# board.net
KiCad netlist of a schematic drawn in EAGLE
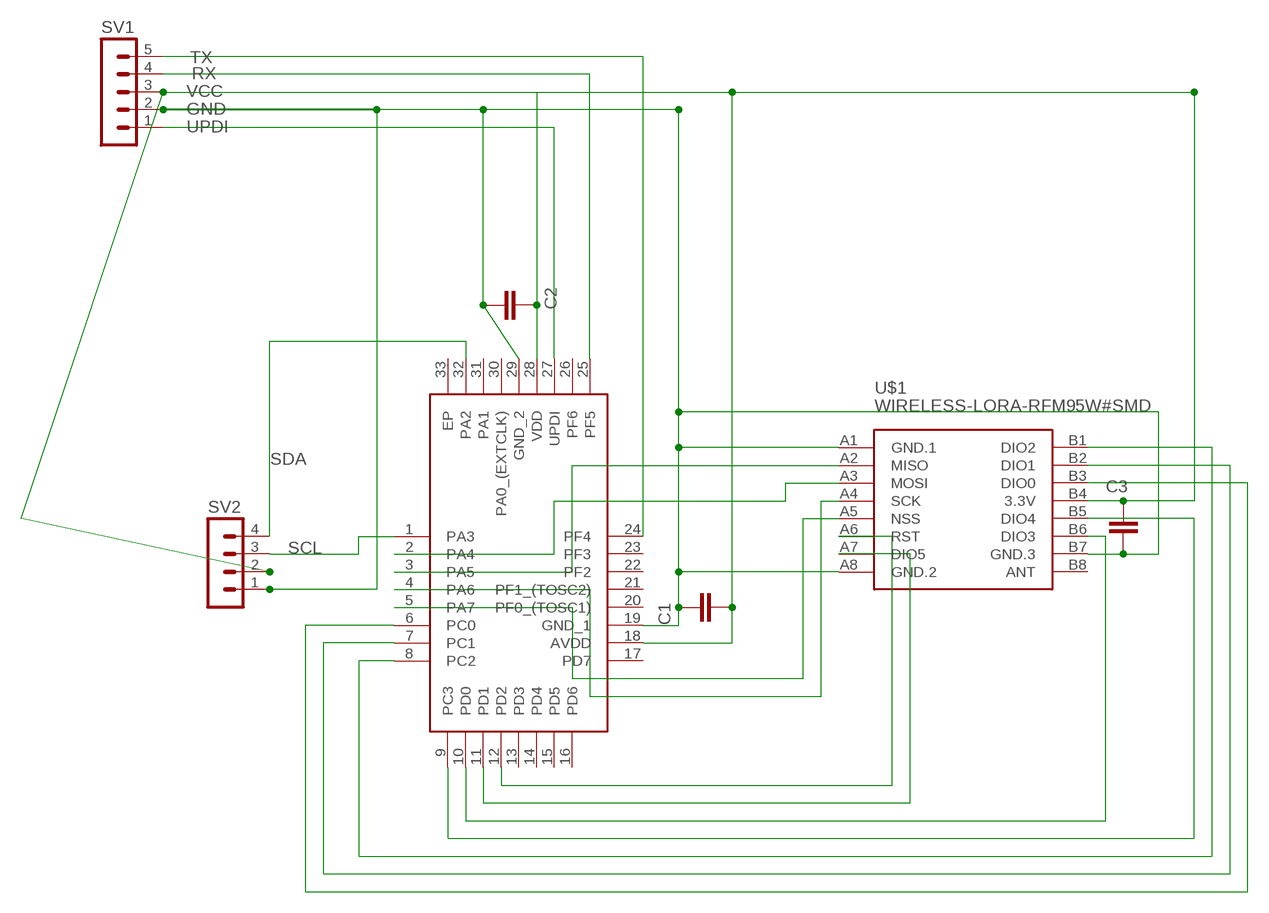
[diagram p0: schematic, sheet 1]

(export (version "E")
  (design (tool "Eeschema 10.0.6"))
  (components
    (comp (ref "C1")
      (value "CC0805KRX7R9BB104")
      (footprint "eagle-import:CAP_0805")
      (fields
        (field (name "DIGIKEY_PART_NUMBER") "311-1140-2-ND")
        (field (name "MANUFACTURER") "Yageo")
        (field (name "CREATED_BY") "PCBLayout.com")
      )
      (libsource (lib "eagle-import") (part "CC0805KRX7R9BB104"))
    )
    (comp (ref "C2")
      (value "CC0805KRX7R9BB104")
      (footprint "eagle-import:CAP_0805")
      (fields
        (field (name "DIGIKEY_PART_NUMBER") "311-1140-2-ND")
        (field (name "MANUFACTURER") "Yageo")
        (field (name "CREATED_BY") "PCBLayout.com")
      )
      (libsource (lib "eagle-import") (part "CC0805KRX7R9BB104"))
    )
    (comp (ref "C3")
      (value "CC0805KRX7R9BB104")
      (footprint "eagle-import:CAP_0805")
      (fields
        (field (name "DIGIKEY_PART_NUMBER") "311-1140-2-ND")
        (field (name "MANUFACTURER") "Yageo")
        (field (name "CREATED_BY") "PCBLayout.com")
      )
      (libsource (lib "eagle-import") (part "CC0805KRX7R9BB104"))
    )
    (comp (ref "IC1")
      (value "ATMEGA3208-MFR")
      (footprint "eagle-import:QFN50P500X500X90-33N")
      (fields (field (name "MOUSER_PART_NUMBER") "556-ATMEGA3208-MFR"))
      (libsource (lib "eagle-import") (part "ATMEGA3208-MFR"))
    )
    (comp (ref "SV1")
      (value "MA05-1")
      (footprint "eagle-import:MA05-1")
      (libsource (lib "eagle-import") (part "MA05-1"))
    )
    (comp (ref "SV2")
      (value "MA04-1")
      (footprint "eagle-import:MA04-1")
      (libsource (lib "eagle-import") (part "MA04-1"))
    )
    (comp (ref "U$1")
      (value "WIRELESS-LORA-RFM95W#SMD")
      (footprint "eagle-import:WIRELESS-LORA-RFM95W#SMD")
      (libsource (lib "eagle-import") (part "WIRELESS-LORA-RFM95W#SMD"))
    )
  )
  (nets
    (net (code "1") (name "/GND") (class "Default")
      (node (ref "C1") (pin "1") (pinfunction "1_1") (pintype "passive"))
      (node (ref "C2") (pin "2") (pinfunction "2_2") (pintype "passive"))
      (node (ref "C3") (pin "2") (pinfunction "2_2") (pintype "passive"))
      (node (ref "IC1") (pin "19") (pinfunction "GND_1_19") (pintype "bidirectional"))
      (node (ref "IC1") (pin "29") (pinfunction "GND_2_29") (pintype "bidirectional"))
      (node (ref "SV1") (pin "2") (pinfunction "2_2") (pintype "passive"))
      (node (ref "SV2") (pin "1") (pinfunction "1_1") (pintype "passive"))
      (node (ref "U$1") (pin "A1") (pinfunction "GND.1_A1") (pintype "power_in"))
      (node (ref "U$1") (pin "A8") (pinfunction "GND.2_A8") (pintype "power_in"))
      (node (ref "U$1") (pin "B7") (pinfunction "GND.3_B7") (pintype "power_in"))
    )
    (net (code "2") (name "/RX") (class "Default")
      (node (ref "IC1") (pin "25") (pinfunction "PF5_25") (pintype "bidirectional"))
      (node (ref "SV1") (pin "4") (pinfunction "4_4") (pintype "passive"))
    )
    (net (code "3") (name "/SCL") (class "Default")
      (node (ref "IC1") (pin "1") (pinfunction "PA3_1") (pintype "bidirectional"))
      (node (ref "SV2") (pin "3") (pinfunction "3_3") (pintype "passive"))
    )
    (net (code "4") (name "/SDA") (class "Default")
      (node (ref "IC1") (pin "32") (pinfunction "PA2_32") (pintype "bidirectional"))
      (node (ref "SV2") (pin "4") (pinfunction "4_4") (pintype "passive"))
    )
    (net (code "5") (name "/TX") (class "Default")
      (node (ref "IC1") (pin "24") (pinfunction "PF4_24") (pintype "bidirectional"))
      (node (ref "SV1") (pin "5") (pinfunction "5_5") (pintype "passive"))
    )
    (net (code "6") (name "/UPDI") (class "Default")
      (node (ref "IC1") (pin "27") (pinfunction "UPDI_27") (pintype "bidirectional"))
      (node (ref "SV1") (pin "1") (pinfunction "1_1") (pintype "passive"))
    )
    (net (code "7") (name "/VCC") (class "Default")
      (node (ref "C1") (pin "2") (pinfunction "2_2") (pintype "passive"))
      (node (ref "C2") (pin "1") (pinfunction "1_1") (pintype "passive"))
      (node (ref "C3") (pin "1") (pinfunction "1_1") (pintype "passive"))
      (node (ref "IC1") (pin "18") (pinfunction "AVDD_18") (pintype "bidirectional"))
      (node (ref "IC1") (pin "28") (pinfunction "VDD_28") (pintype "bidirectional"))
      (node (ref "SV1") (pin "3") (pinfunction "3_3") (pintype "passive"))
      (node (ref "SV2") (pin "2") (pinfunction "2_2") (pintype "passive"))
      (node (ref "U$1") (pin "B4") (pinfunction "3.3V_B4") (pintype "power_in"))
    )
    (net (code "8") (name "Net-(IC1-PA4)") (class "Default")
      (node (ref "IC1") (pin "2") (pinfunction "PA4_2") (pintype "bidirectional"))
      (node (ref "U$1") (pin "A3") (pinfunction "MOSI_A3") (pintype "bidirectional"))
    )
    (net (code "9") (name "Net-(IC1-PA5)") (class "Default")
      (node (ref "IC1") (pin "3") (pinfunction "PA5_3") (pintype "bidirectional"))
      (node (ref "U$1") (pin "A2") (pinfunction "MISO_A2") (pintype "bidirectional"))
    )
    (net (code "10") (name "Net-(IC1-PA6)") (class "Default")
      (node (ref "IC1") (pin "4") (pinfunction "PA6_4") (pintype "bidirectional"))
      (node (ref "U$1") (pin "A4") (pinfunction "SCK_A4") (pintype "bidirectional"))
    )
    (net (code "11") (name "Net-(IC1-PA7)") (class "Default")
      (node (ref "IC1") (pin "5") (pinfunction "PA7_5") (pintype "bidirectional"))
      (node (ref "U$1") (pin "A5") (pinfunction "NSS_A5") (pintype "bidirectional"))
    )
    (net (code "12") (name "Net-(IC1-PC0)") (class "Default")
      (node (ref "IC1") (pin "6") (pinfunction "PC0_6") (pintype "bidirectional"))
      (node (ref "U$1") (pin "B3") (pinfunction "DIO0_B3") (pintype "bidirectional"))
    )
    (net (code "13") (name "Net-(IC1-PC1)") (class "Default")
      (node (ref "IC1") (pin "7") (pinfunction "PC1_7") (pintype "bidirectional"))
      (node (ref "U$1") (pin "B2") (pinfunction "DIO1_B2") (pintype "bidirectional"))
    )
    (net (code "14") (name "Net-(IC1-PC2)") (class "Default")
      (node (ref "IC1") (pin "8") (pinfunction "PC2_8") (pintype "bidirectional"))
      (node (ref "U$1") (pin "B1") (pinfunction "DIO2_B1") (pintype "bidirectional"))
    )
    (net (code "15") (name "Net-(IC1-PC3)") (class "Default")
      (node (ref "IC1") (pin "9") (pinfunction "PC3_9") (pintype "bidirectional"))
      (node (ref "U$1") (pin "B5") (pinfunction "DIO4_B5") (pintype "bidirectional"))
    )
    (net (code "16") (name "Net-(IC1-PD0)") (class "Default")
      (node (ref "IC1") (pin "10") (pinfunction "PD0_10") (pintype "bidirectional"))
      (node (ref "U$1") (pin "B6") (pinfunction "DIO3_B6") (pintype "bidirectional"))
    )
    (net (code "17") (name "Net-(IC1-PD1)") (class "Default")
      (node (ref "IC1") (pin "11") (pinfunction "PD1_11") (pintype "bidirectional"))
      (node (ref "U$1") (pin "A7") (pinfunction "DIO5_A7") (pintype "bidirectional"))
    )
    (net (code "18") (name "Net-(IC1-PD2)") (class "Default")
      (node (ref "IC1") (pin "12") (pinfunction "PD2_12") (pintype "bidirectional"))
      (node (ref "U$1") (pin "A6") (pinfunction "RST_A6") (pintype "bidirectional"))
    )
    (net (code "19") (name "unconnected-(IC1-EP-Pad33)") (class "Default")
      (node (ref "IC1") (pin "33") (pinfunction "EP_33") (pintype "bidirectional"))
    )
    (net (code "20") (name "unconnected-(IC1-PA0_(EXTCLK)-Pad30)") (class "Default")
      (node (ref "IC1") (pin "30") (pinfunction "PA0_(EXTCLK)_30") (pintype "bidirectional"))
    )
    (net (code "21") (name "unconnected-(IC1-PA1-Pad31)") (class "Default")
      (node (ref "IC1") (pin "31") (pinfunction "PA1_31") (pintype "bidirectional"))
    )
    (net (code "22") (name "unconnected-(IC1-PD3-Pad13)") (class "Default")
      (node (ref "IC1") (pin "13") (pinfunction "PD3_13") (pintype "bidirectional"))
    )
    (net (code "23") (name "unconnected-(IC1-PD4-Pad14)") (class "Default")
      (node (ref "IC1") (pin "14") (pinfunction "PD4_14") (pintype "bidirectional"))
    )
    (net (code "24") (name "unconnected-(IC1-PD5-Pad15)") (class "Default")
      (node (ref "IC1") (pin "15") (pinfunction "PD5_15") (pintype "bidirectional"))
    )
    (net (code "25") (name "unconnected-(IC1-PD6-Pad16)") (class "Default")
      (node (ref "IC1") (pin "16") (pinfunction "PD6_16") (pintype "bidirectional"))
    )
    (net (code "26") (name "unconnected-(IC1-PD7-Pad17)") (class "Default")
      (node (ref "IC1") (pin "17") (pinfunction "PD7_17") (pintype "bidirectional"))
    )
    (net (code "27") (name "unconnected-(IC1-PF0_(TOSC1)-Pad20)") (class "Default")
      (node (ref "IC1") (pin "20") (pinfunction "PF0_(TOSC1)_20") (pintype "bidirectional"))
    )
    (net (code "28") (name "unconnected-(IC1-PF1_(TOSC2)-Pad21)") (class "Default")
      (node (ref "IC1") (pin "21") (pinfunction "PF1_(TOSC2)_21") (pintype "bidirectional"))
    )
    (net (code "29") (name "unconnected-(IC1-PF2-Pad22)") (class "Default")
      (node (ref "IC1") (pin "22") (pinfunction "PF2_22") (pintype "bidirectional"))
    )
    (net (code "30") (name "unconnected-(IC1-PF3-Pad23)") (class "Default")
      (node (ref "IC1") (pin "23") (pinfunction "PF3_23") (pintype "bidirectional"))
    )
    (net (code "31") (name "unconnected-(IC1-PF6-Pad26)") (class "Default")
      (node (ref "IC1") (pin "26") (pinfunction "PF6_26") (pintype "bidirectional"))
    )
    (net (code "32") (name "unconnected-(U$1-ANT-PadB8)") (class "Default")
      (node (ref "U$1") (pin "B8") (pinfunction "ANT_B8") (pintype "passive"))
    )
  )
)
